# usbswitch_july2016.net
KiCad netlist of a schematic drawn in EAGLE
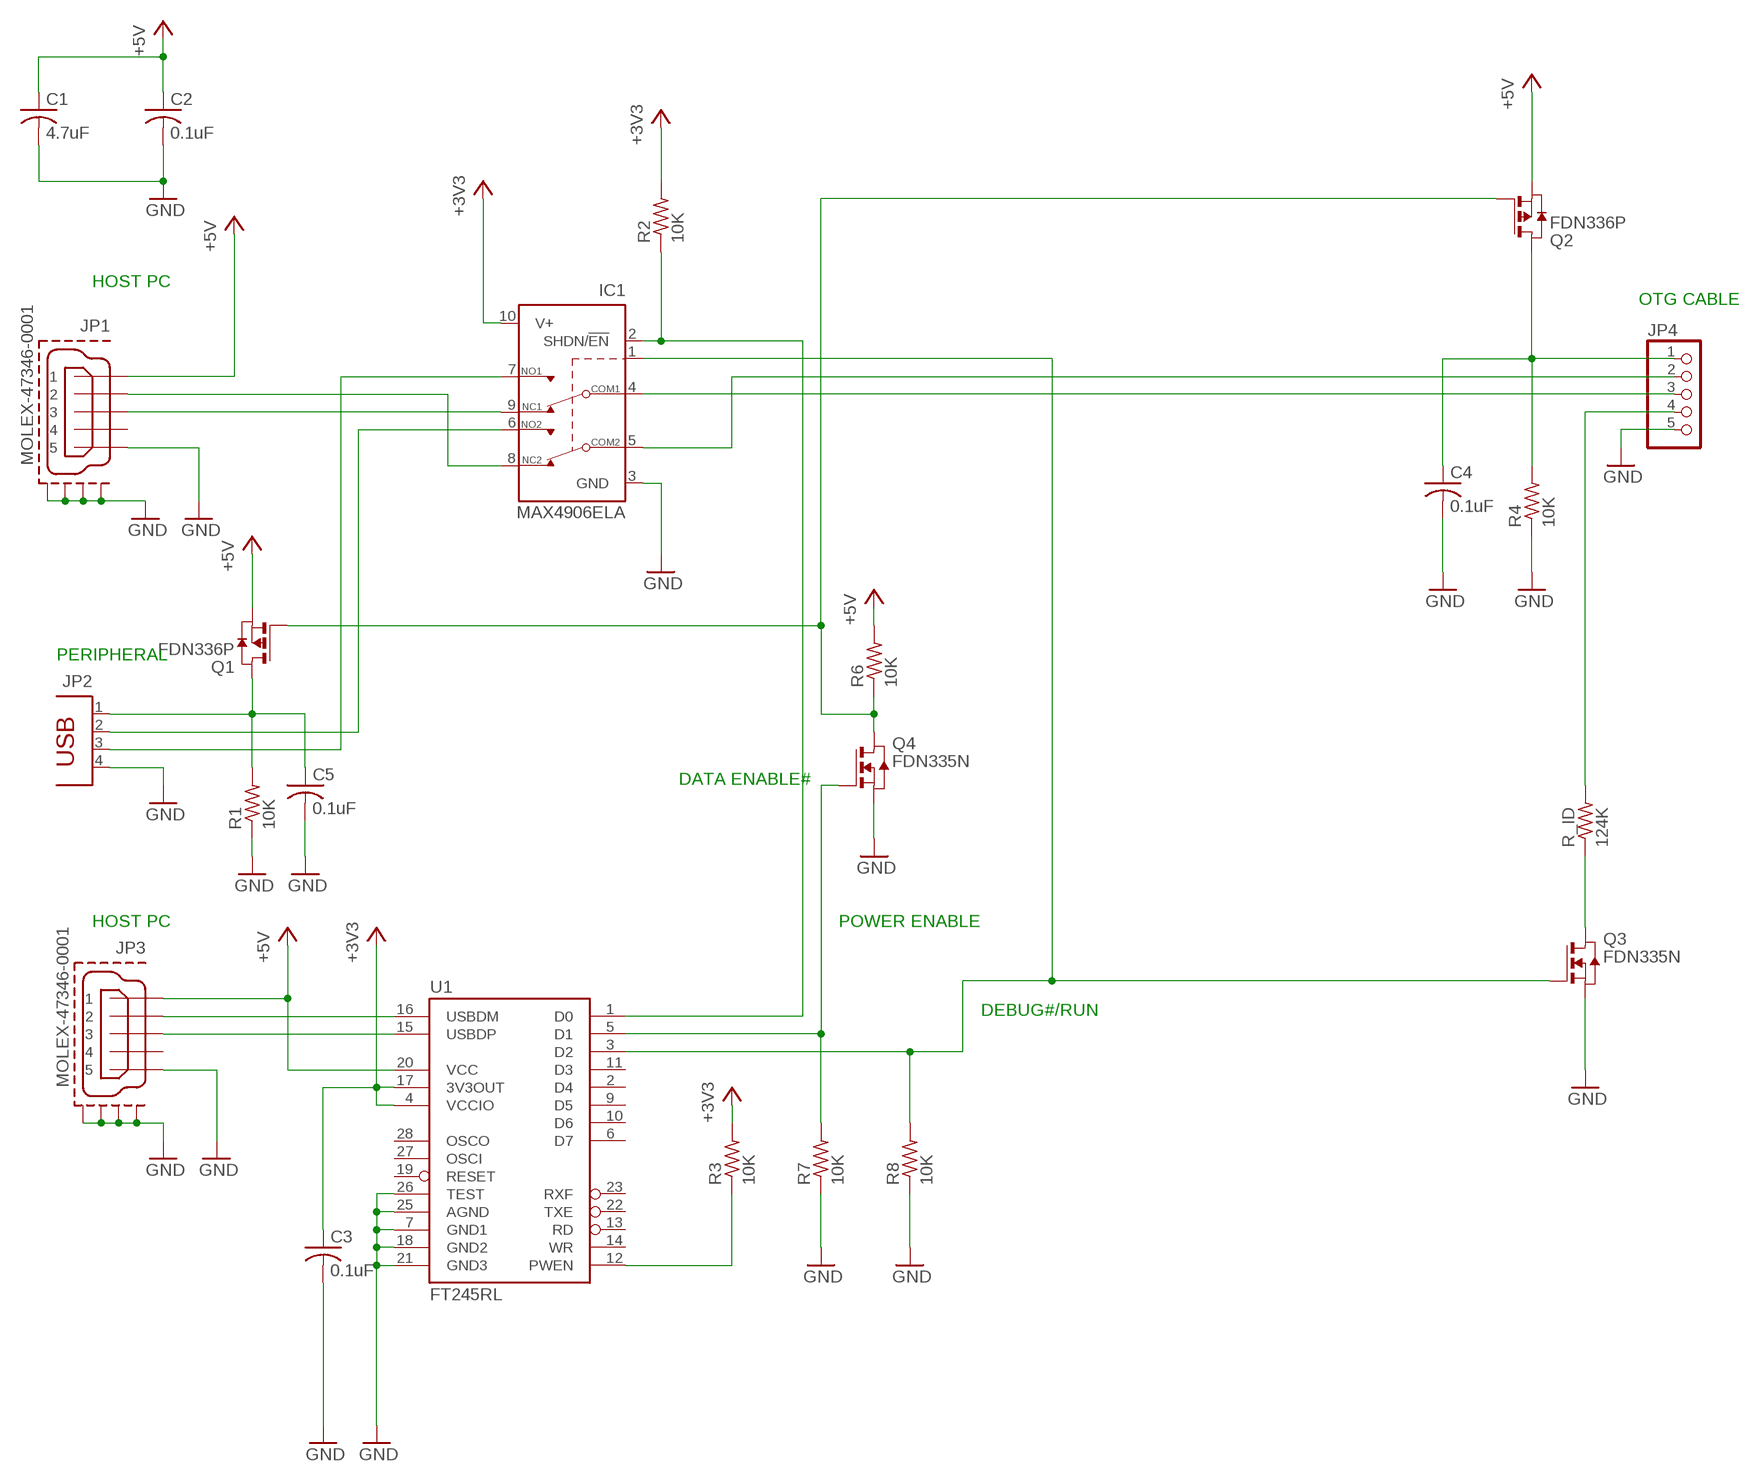
[diagram p0: schematic, sheet 1]

(export (version "E")
  (design (tool "Eeschema 10.0.6"))
  (components
    (comp (ref "C1")
      (value "4.7uF")
      (footprint "eagle-import:C1210K")
      (libsource (lib "eagle-import") (part "C-USC1210K"))
    )
    (comp (ref "C2")
      (value "0.1uF")
      (footprint "eagle-import:C0805K")
      (libsource (lib "eagle-import") (part "C-USC0805K"))
    )
    (comp (ref "C3")
      (value "0.1uF")
      (footprint "eagle-import:C0805K")
      (libsource (lib "eagle-import") (part "C-USC0805K"))
    )
    (comp (ref "C4")
      (value "0.1uF")
      (footprint "eagle-import:C0805K")
      (libsource (lib "eagle-import") (part "C-USC0805K"))
    )
    (comp (ref "C5")
      (value "0.1uF")
      (footprint "eagle-import:C0805K")
      (libsource (lib "eagle-import") (part "C-USC0805K"))
    )
    (comp (ref "IC1")
      (value "MAX4906ELA")
      (footprint "eagle-import:UDFN10")
      (libsource (lib "eagle-import") (part "MAX4906ELA"))
    )
    (comp (ref "JP1")
      (value "MOLEX-47346-0001")
      (footprint "eagle-import:MOLEX-47364-0001")
      (libsource (lib "eagle-import") (part "MOLEX-47346-0001"))
    )
    (comp (ref "JP2")
      (value "PN87520")
      (footprint "eagle-import:PN87520")
      (libsource (lib "eagle-import") (part "PN87520"))
    )
    (comp (ref "JP3")
      (value "MOLEX-47346-0001")
      (footprint "eagle-import:MOLEX-47364-0001")
      (libsource (lib "eagle-import") (part "MOLEX-47346-0001"))
    )
    (comp (ref "JP4")
      (value "PINHD-1X5")
      (footprint "eagle-import:1X05")
      (libsource (lib "eagle-import") (part "PINHD-1X5"))
    )
    (comp (ref "Q1")
      (value "FDN336P")
      (footprint "eagle-import:SOT-23")
      (libsource (lib "eagle-import") (part "PMOSSOT23"))
    )
    (comp (ref "Q2")
      (value "FDN336P")
      (footprint "eagle-import:SOT-23")
      (libsource (lib "eagle-import") (part "PMOSSOT23"))
    )
    (comp (ref "Q3")
      (value "FDN335N")
      (footprint "eagle-import:SOT-23")
      (libsource (lib "eagle-import") (part "NMOSSTO23"))
    )
    (comp (ref "Q4")
      (value "FDN335N")
      (footprint "eagle-import:SOT-23")
      (libsource (lib "eagle-import") (part "NMOSSTO23"))
    )
    (comp (ref "R1")
      (value "10K")
      (footprint "eagle-import:R0805W")
      (libsource (lib "eagle-import") (part "R-US_R0805W"))
    )
    (comp (ref "R2")
      (value "10K")
      (footprint "eagle-import:R0805W")
      (libsource (lib "eagle-import") (part "R-US_R0805W"))
    )
    (comp (ref "R3")
      (value "10K")
      (footprint "eagle-import:R0805W")
      (libsource (lib "eagle-import") (part "R-US_R0805W"))
    )
    (comp (ref "R4")
      (value "10K")
      (footprint "eagle-import:R0805W")
      (libsource (lib "eagle-import") (part "R-US_R0805W"))
    )
    (comp (ref "R6")
      (value "10K")
      (footprint "eagle-import:R0805W")
      (libsource (lib "eagle-import") (part "R-US_R0805W"))
    )
    (comp (ref "R7")
      (value "10K")
      (footprint "eagle-import:R0805W")
      (libsource (lib "eagle-import") (part "R-US_R0805W"))
    )
    (comp (ref "R8")
      (value "10K")
      (footprint "eagle-import:R0805W")
      (libsource (lib "eagle-import") (part "R-US_R0805W"))
    )
    (comp (ref "R_ID")
      (value "124K")
      (footprint "eagle-import:R0805W")
      (libsource (lib "eagle-import") (part "R-US_R0805W"))
    )
    (comp (ref "U1")
      (value "FT245RL")
      (footprint "eagle-import:SSOP28DB")
      (libsource (lib "eagle-import") (part "FT245RL"))
    )
  )
  (nets
    (net (code "1") (name "+3V3") (class "Default")
      (node (ref "C3") (pin "1") (pinfunction "1_1") (pintype "passive"))
      (node (ref "IC1") (pin "10") (pinfunction "V+_10") (pintype "input"))
      (node (ref "R2") (pin "2") (pinfunction "2_2") (pintype "passive"))
      (node (ref "R3") (pin "2") (pinfunction "2_2") (pintype "passive"))
      (node (ref "U1") (pin "17") (pinfunction "3V3OUT_17") (pintype "output"))
      (node (ref "U1") (pin "4") (pinfunction "VCCIO_4") (pintype "power_in"))
    )
    (net (code "2") (name "+5V") (class "Default")
      (node (ref "C1") (pin "1") (pinfunction "1_1") (pintype "passive"))
      (node (ref "C2") (pin "1") (pinfunction "1_1") (pintype "passive"))
      (node (ref "JP1") (pin "1") (pinfunction "1_1") (pintype "input"))
      (node (ref "JP3") (pin "1") (pinfunction "1_1") (pintype "input"))
      (node (ref "Q1") (pin "2") (pinfunction "S_2") (pintype "passive"))
      (node (ref "Q2") (pin "2") (pinfunction "S_2") (pintype "passive"))
      (node (ref "R6") (pin "2") (pinfunction "2_2") (pintype "passive"))
      (node (ref "U1") (pin "20") (pinfunction "VCC_20") (pintype "power_in"))
    )
    (net (code "3") (name "GND") (class "Default")
      (node (ref "C1") (pin "2") (pinfunction "2_2") (pintype "passive"))
      (node (ref "C2") (pin "2") (pinfunction "2_2") (pintype "passive"))
      (node (ref "C3") (pin "2") (pinfunction "2_2") (pintype "passive"))
      (node (ref "C4") (pin "2") (pinfunction "2_2") (pintype "passive"))
      (node (ref "C5") (pin "2") (pinfunction "2_2") (pintype "passive"))
      (node (ref "IC1") (pin "3") (pinfunction "GND_3") (pintype "power_in"))
      (node (ref "JP1") (pin "5") (pinfunction "5_5") (pintype "input"))
      (node (ref "JP1") (pin "GND1") (pinfunction "GND1_GND1") (pintype "bidirectional"))
      (node (ref "JP1") (pin "GND2") (pinfunction "GND2_GND2") (pintype "bidirectional"))
      (node (ref "JP1") (pin "GND3") (pinfunction "GND3_GND3") (pintype "bidirectional"))
      (node (ref "JP1") (pin "GND4") (pinfunction "GND4_GND4") (pintype "bidirectional"))
      (node (ref "JP2") (pin "4") (pinfunction "4_4") (pintype "passive"))
      (node (ref "JP3") (pin "5") (pinfunction "5_5") (pintype "input"))
      (node (ref "JP3") (pin "GND1") (pinfunction "GND1_GND1") (pintype "bidirectional"))
      (node (ref "JP3") (pin "GND2") (pinfunction "GND2_GND2") (pintype "bidirectional"))
      (node (ref "JP3") (pin "GND3") (pinfunction "GND3_GND3") (pintype "bidirectional"))
      (node (ref "JP3") (pin "GND4") (pinfunction "GND4_GND4") (pintype "bidirectional"))
      (node (ref "JP4") (pin "5") (pinfunction "5_5") (pintype "passive"))
      (node (ref "Q3") (pin "2") (pinfunction "S_2") (pintype "passive"))
      (node (ref "Q4") (pin "2") (pinfunction "S_2") (pintype "passive"))
      (node (ref "R1") (pin "1") (pinfunction "1_1") (pintype "passive"))
      (node (ref "R4") (pin "1") (pinfunction "1_1") (pintype "passive"))
      (node (ref "R7") (pin "1") (pinfunction "1_1") (pintype "passive"))
      (node (ref "R8") (pin "1") (pinfunction "1_1") (pintype "passive"))
      (node (ref "U1") (pin "18") (pinfunction "GND2_18") (pintype "power_in"))
      (node (ref "U1") (pin "21") (pinfunction "GND3_21") (pintype "power_in"))
      (node (ref "U1") (pin "25") (pinfunction "AGND_25") (pintype "power_in"))
      (node (ref "U1") (pin "26") (pinfunction "TEST_26") (pintype "input"))
      (node (ref "U1") (pin "7") (pinfunction "GND1_7") (pintype "power_in"))
    )
    (net (code "4") (name "Net-(IC1-COM1)") (class "Default")
      (node (ref "IC1") (pin "4") (pinfunction "COM1_4") (pintype "bidirectional"))
      (node (ref "JP4") (pin "3") (pinfunction "3_3") (pintype "passive"))
    )
    (net (code "5") (name "Net-(IC1-COM2)") (class "Default")
      (node (ref "IC1") (pin "5") (pinfunction "COM2_5") (pintype "bidirectional"))
      (node (ref "JP4") (pin "2") (pinfunction "2_2") (pintype "passive"))
    )
    (net (code "6") (name "Net-(IC1-IN)") (class "Default")
      (node (ref "IC1") (pin "1") (pinfunction "IN_1") (pintype "input"))
      (node (ref "Q3") (pin "3") (pinfunction "G_3") (pintype "passive"))
      (node (ref "R8") (pin "2") (pinfunction "2_2") (pintype "passive"))
      (node (ref "U1") (pin "3") (pinfunction "D2_3") (pintype "output"))
    )
    (net (code "7") (name "Net-(IC1-NC1)") (class "Default")
      (node (ref "IC1") (pin "9") (pinfunction "NC1_9") (pintype "bidirectional"))
      (node (ref "JP1") (pin "3") (pinfunction "3_3") (pintype "input"))
    )
    (net (code "8") (name "Net-(IC1-NC2)") (class "Default")
      (node (ref "IC1") (pin "8") (pinfunction "NC2_8") (pintype "bidirectional"))
      (node (ref "JP1") (pin "2") (pinfunction "2_2") (pintype "input"))
    )
    (net (code "9") (name "Net-(IC1-NO1)") (class "Default")
      (node (ref "IC1") (pin "7") (pinfunction "NO1_7") (pintype "bidirectional"))
      (node (ref "JP2") (pin "3") (pinfunction "3_3") (pintype "passive"))
    )
    (net (code "10") (name "Net-(IC1-NO2)") (class "Default")
      (node (ref "IC1") (pin "6") (pinfunction "NO2_6") (pintype "bidirectional"))
      (node (ref "JP2") (pin "2") (pinfunction "2_2") (pintype "passive"))
    )
    (net (code "11") (name "Net-(IC1-SHDN{slash}~{EN})") (class "Default")
      (node (ref "IC1") (pin "2") (pinfunction "SHDN/~{EN}_2") (pintype "input"))
      (node (ref "R2") (pin "1") (pinfunction "1_1") (pintype "passive"))
      (node (ref "U1") (pin "1") (pinfunction "D0_1") (pintype "output"))
    )
    (net (code "12") (name "Net-(JP4-Pad4)") (class "Default")
      (node (ref "JP4") (pin "4") (pinfunction "4_4") (pintype "passive"))
      (node (ref "R_ID") (pin "2") (pinfunction "2_2") (pintype "passive"))
    )
    (net (code "13") (name "Net-(Q1-D)") (class "Default")
      (node (ref "C5") (pin "1") (pinfunction "1_1") (pintype "passive"))
      (node (ref "JP2") (pin "1") (pinfunction "1_1") (pintype "passive"))
      (node (ref "Q1") (pin "1") (pinfunction "D_1") (pintype "passive"))
      (node (ref "R1") (pin "2") (pinfunction "2_2") (pintype "passive"))
    )
    (net (code "14") (name "Net-(Q1-G)") (class "Default")
      (node (ref "Q1") (pin "3") (pinfunction "G_3") (pintype "passive"))
      (node (ref "Q2") (pin "3") (pinfunction "G_3") (pintype "passive"))
      (node (ref "Q4") (pin "1") (pinfunction "D_1") (pintype "passive"))
      (node (ref "R6") (pin "1") (pinfunction "1_1") (pintype "passive"))
    )
    (net (code "15") (name "Net-(Q2-D)") (class "Default")
      (node (ref "C4") (pin "1") (pinfunction "1_1") (pintype "passive"))
      (node (ref "JP4") (pin "1") (pinfunction "1_1") (pintype "passive"))
      (node (ref "Q2") (pin "1") (pinfunction "D_1") (pintype "passive"))
      (node (ref "R4") (pin "2") (pinfunction "2_2") (pintype "passive"))
    )
    (net (code "16") (name "Net-(Q3-D)") (class "Default")
      (node (ref "Q3") (pin "1") (pinfunction "D_1") (pintype "passive"))
      (node (ref "R_ID") (pin "1") (pinfunction "1_1") (pintype "passive"))
    )
    (net (code "17") (name "Net-(Q4-G)") (class "Default")
      (node (ref "Q4") (pin "3") (pinfunction "G_3") (pintype "passive"))
      (node (ref "R7") (pin "2") (pinfunction "2_2") (pintype "passive"))
      (node (ref "U1") (pin "5") (pinfunction "D1_5") (pintype "input"))
    )
    (net (code "18") (name "Net-(U1-PWEN)") (class "Default")
      (node (ref "R3") (pin "1") (pinfunction "1_1") (pintype "passive"))
      (node (ref "U1") (pin "12") (pinfunction "PWEN_12") (pintype "bidirectional"))
    )
    (net (code "19") (name "Net-(U1-USBDM)") (class "Default")
      (node (ref "JP3") (pin "2") (pinfunction "2_2") (pintype "input"))
      (node (ref "U1") (pin "16") (pinfunction "USBDM_16") (pintype "bidirectional"))
    )
    (net (code "20") (name "Net-(U1-USBDP)") (class "Default")
      (node (ref "JP3") (pin "3") (pinfunction "3_3") (pintype "input"))
      (node (ref "U1") (pin "15") (pinfunction "USBDP_15") (pintype "bidirectional"))
    )
    (net (code "21") (name "unconnected-(JP1-Pad4)") (class "Default")
      (node (ref "JP1") (pin "4") (pinfunction "4_4") (pintype "input"))
    )
    (net (code "22") (name "unconnected-(JP3-Pad4)") (class "Default")
      (node (ref "JP3") (pin "4") (pinfunction "4_4") (pintype "input"))
    )
    (net (code "23") (name "unconnected-(U1-D3-Pad11)") (class "Default")
      (node (ref "U1") (pin "11") (pinfunction "D3_11") (pintype "input"))
    )
    (net (code "24") (name "unconnected-(U1-D4-Pad2)") (class "Default")
      (node (ref "U1") (pin "2") (pinfunction "D4_2") (pintype "output"))
    )
    (net (code "25") (name "unconnected-(U1-D5-Pad9)") (class "Default")
      (node (ref "U1") (pin "9") (pinfunction "D5_9") (pintype "input"))
    )
    (net (code "26") (name "unconnected-(U1-D6-Pad10)") (class "Default")
      (node (ref "U1") (pin "10") (pinfunction "D6_10") (pintype "input"))
    )
    (net (code "27") (name "unconnected-(U1-D7-Pad6)") (class "Default")
      (node (ref "U1") (pin "6") (pinfunction "D7_6") (pintype "input"))
    )
    (net (code "28") (name "unconnected-(U1-OSCI-Pad27)") (class "Default")
      (node (ref "U1") (pin "27") (pinfunction "OSCI_27") (pintype "input"))
    )
    (net (code "29") (name "unconnected-(U1-OSCO-Pad28)") (class "Default")
      (node (ref "U1") (pin "28") (pinfunction "OSCO_28") (pintype "output"))
    )
    (net (code "30") (name "unconnected-(U1-RD-Pad13)") (class "Default")
      (node (ref "U1") (pin "13") (pinfunction "RD_13") (pintype "bidirectional"))
    )
    (net (code "31") (name "unconnected-(U1-RESET-Pad19)") (class "Default")
      (node (ref "U1") (pin "19") (pinfunction "RESET_19") (pintype "input"))
    )
    (net (code "32") (name "unconnected-(U1-RXF-Pad23)") (class "Default")
      (node (ref "U1") (pin "23") (pinfunction "RXF_23") (pintype "bidirectional"))
    )
    (net (code "33") (name "unconnected-(U1-TXE-Pad22)") (class "Default")
      (node (ref "U1") (pin "22") (pinfunction "TXE_22") (pintype "bidirectional"))
    )
    (net (code "34") (name "unconnected-(U1-WR-Pad14)") (class "Default")
      (node (ref "U1") (pin "14") (pinfunction "WR_14") (pintype "bidirectional"))
    )
  )
)
